# Power.net
KiCad netlist of a schematic drawn in Altium Designer
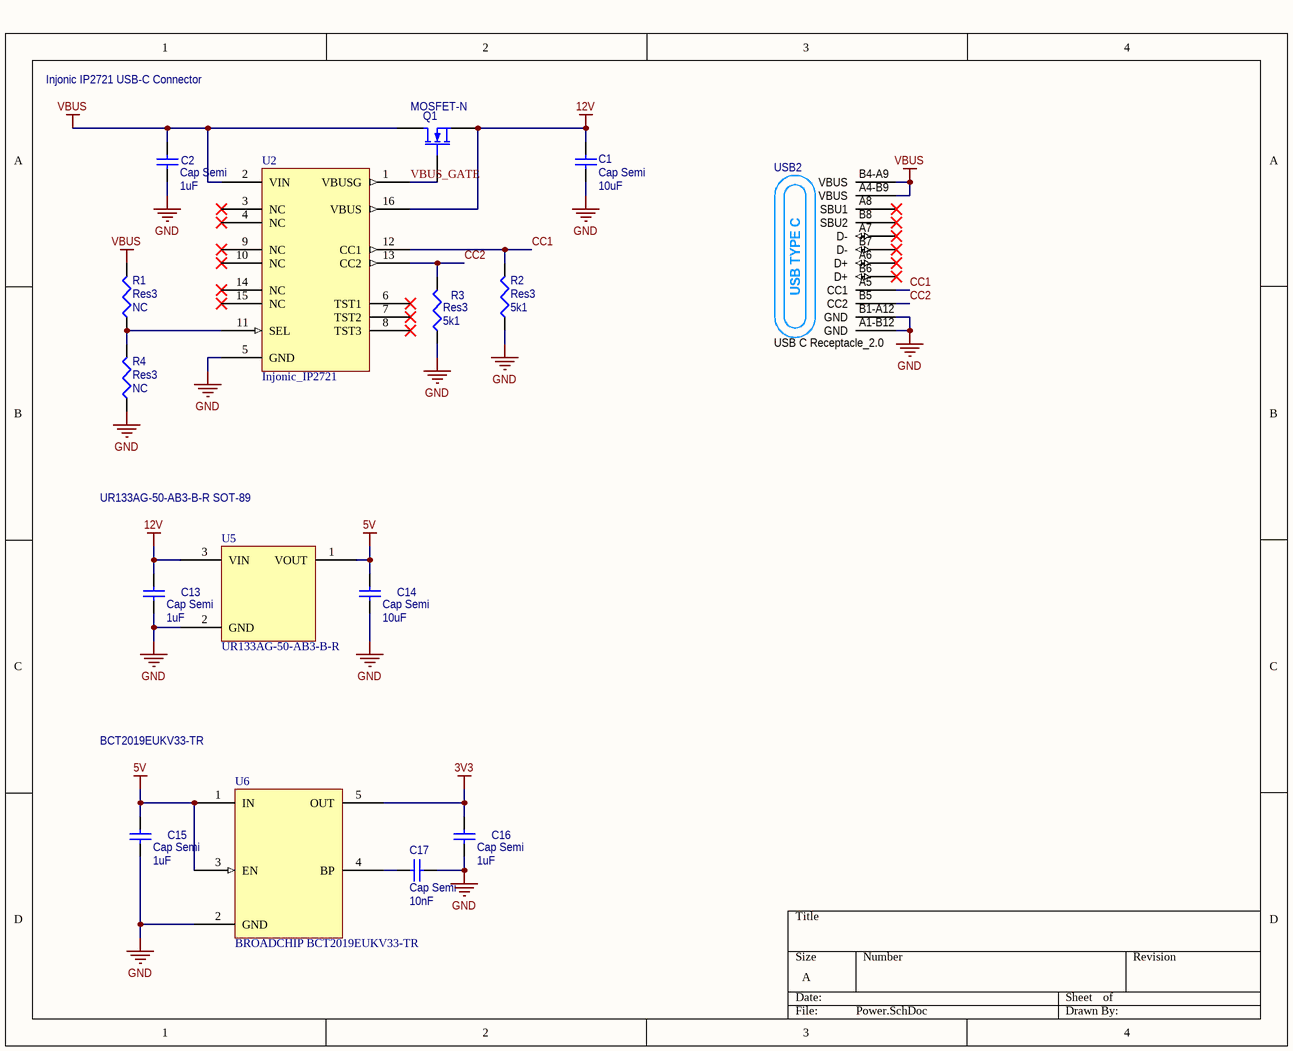
[diagram p0: Power.SchDoc]

(export (version "E")
  (design (tool "Eeschema 10.0.6"))
  (components
    (comp (ref "C1")
      (value "Cap Semi")
      (footprint "1608[0603]")
      (description "Capacitor (Semiconductor SIM Model)")
      (fields (field (name "ALTIUM_VALUE") "10uF") (field (name "PUBLISHER") "Altium Limited"))
      (libsource (lib "Miscellaneous Devices") (part "Cap Semi"))
    )
    (comp (ref "C2")
      (value "Cap Semi")
      (footprint "0402")
      (description "Capacitor (Semiconductor SIM Model)")
      (fields (field (name "ALTIUM_VALUE") "1uF") (field (name "PUBLISHER") "Altium Limited"))
      (libsource (lib "Miscellaneous Devices") (part "Cap Semi"))
    )
    (comp (ref "C13")
      (value "Cap Semi")
      (footprint "0402")
      (description "Capacitor (Semiconductor SIM Model)")
      (fields (field (name "ALTIUM_VALUE") "1uF") (field (name "PUBLISHER") "Altium Limited"))
      (libsource (lib "Miscellaneous Devices") (part "Cap Semi"))
    )
    (comp (ref "C14")
      (value "Cap Semi")
      (footprint "1608[0603]")
      (description "Capacitor (Semiconductor SIM Model)")
      (fields (field (name "ALTIUM_VALUE") "10uF") (field (name "PUBLISHER") "Altium Limited"))
      (libsource (lib "Miscellaneous Devices") (part "Cap Semi"))
    )
    (comp (ref "C15")
      (value "Cap Semi")
      (footprint "0402")
      (description "Capacitor (Semiconductor SIM Model)")
      (fields (field (name "ALTIUM_VALUE") "1uF") (field (name "PUBLISHER") "Altium Limited"))
      (libsource (lib "Miscellaneous Devices") (part "Cap Semi"))
    )
    (comp (ref "C16")
      (value "Cap Semi")
      (footprint "0402")
      (description "Capacitor (Semiconductor SIM Model)")
      (fields (field (name "ALTIUM_VALUE") "1uF") (field (name "PUBLISHER") "Altium Limited"))
      (libsource (lib "Miscellaneous Devices") (part "Cap Semi"))
    )
    (comp (ref "C17")
      (value "Cap Semi")
      (footprint "0402")
      (description "Capacitor (Semiconductor SIM Model)")
      (fields (field (name "ALTIUM_VALUE") "10nF") (field (name "PUBLISHER") "Altium Limited"))
      (libsource (lib "Miscellaneous Devices") (part "Cap Semi"))
    )
    (comp (ref "Q1")
      (value "MOSFET-N")
      (footprint "BSS214NWH6327")
      (description "N-Channel MOSFET")
      (fields (field (name "PUBLISHER") "Altium Limited"))
      (libsource (lib "Miscellaneous Devices") (part "MOSFET-N"))
    )
    (comp (ref "R1")
      (value "Res3")
      (footprint "J1-0603")
      (description "Resistor")
      (fields (field (name "ALTIUM_VALUE") "NC") (field (name "PUBLISHER") "Altium Limited"))
      (libsource (lib "Miscellaneous Devices") (part "Res3"))
    )
    (comp (ref "R2")
      (value "Res3")
      (footprint "J1-0603")
      (description "Resistor")
      (fields (field (name "ALTIUM_VALUE") "5k1") (field (name "PUBLISHER") "Altium Limited"))
      (libsource (lib "Miscellaneous Devices") (part "Res3"))
    )
    (comp (ref "R3")
      (value "Res3")
      (footprint "J1-0603")
      (description "Resistor")
      (fields (field (name "ALTIUM_VALUE") "5k1") (field (name "PUBLISHER") "Altium Limited"))
      (libsource (lib "Miscellaneous Devices") (part "Res3"))
    )
    (comp (ref "R4")
      (value "Res3")
      (footprint "J1-0603")
      (description "Resistor")
      (fields (field (name "ALTIUM_VALUE") "NC") (field (name "PUBLISHER") "Altium Limited"))
      (libsource (lib "Miscellaneous Devices") (part "Res3"))
    )
    (comp (ref "U2")
      (value "Injonic_IP2721")
      (footprint "TSOP65P640X120-16N")
      (description "USB-C Controller")
      (libsource (lib "Nixie_Clock") (part "Injonic_P2721"))
    )
    (comp (ref "U5")
      (value "UR133AG-50-AB3-B-R")
      (footprint "SOT89-150P415X160-3N")
      (description "12V-5V Voltage Regulator")
      (libsource (lib "Nixie_Clock") (part "UR133AG-50-AB3-B-R SOT-89"))
    )
    (comp (ref "U6")
      (value "BROADCHIP BCT2019EUKV33-TR")
      (footprint "SOT95P290X115-5N")
      (description "5V-3.3V Voltage Regulator")
      (libsource (lib "Nixie_Clock") (part "BCT2019EUKV33-TR"))
    )
    (comp (ref "USB2")
      (value "USB C Receptacle_2.0")
      (footprint "TYPE-C16PIN-CONNECTOR")
      (libsource (lib "kwa") (part "USB C Receptacle_2.0"))
    )
  )
  (nets
    (net (code "2") (name "/CC1") (class "Default")
      (node (ref "R2") (pin "2") (pinfunction "2_2") (pintype "passive"))
      (node (ref "U2") (pin "12") (pinfunction "CC1_12") (pintype "output"))
      (node (ref "USB2") (pin "A5") (pinfunction "CC1_A5") (pintype "passive"))
    )
    (net (code "3") (name "/CC2") (class "Default")
      (node (ref "R3") (pin "2") (pinfunction "2_2") (pintype "passive"))
      (node (ref "U2") (pin "13") (pinfunction "CC2_13") (pintype "output"))
      (node (ref "USB2") (pin "B5") (pinfunction "CC2_B5") (pintype "passive"))
    )
    (net (code "4") (name "/VBUS_GATE") (class "Default")
      (node (ref "Q1") (pin "2") (pinfunction "G_2") (pintype "passive"))
      (node (ref "U2") (pin "1") (pinfunction "VBUSG_1") (pintype "output"))
    )
    (net (code "5") (name "3V3") (class "Default")
      (node (ref "C16") (pin "2") (pinfunction "2_2") (pintype "passive"))
      (node (ref "U6") (pin "5") (pinfunction "OUT_5") (pintype "power_in"))
    )
    (net (code "6") (name "5V") (class "Default")
      (node (ref "C14") (pin "2") (pinfunction "2_2") (pintype "passive"))
      (node (ref "C15") (pin "2") (pinfunction "2_2") (pintype "passive"))
      (node (ref "U5") (pin "1") (pinfunction "VOUT_1") (pintype "power_in"))
      (node (ref "U6") (pin "1") (pinfunction "IN_1") (pintype "power_in"))
      (node (ref "U6") (pin "3") (pinfunction "EN_3") (pintype "input"))
    )
    (net (code "7") (name "12V") (class "Default")
      (node (ref "C1") (pin "2") (pinfunction "2_2") (pintype "passive"))
      (node (ref "C13") (pin "2") (pinfunction "2_2") (pintype "passive"))
      (node (ref "Q1") (pin "3") (pinfunction "S_3") (pintype "passive"))
      (node (ref "U2") (pin "16") (pinfunction "VBUS_16") (pintype "output"))
      (node (ref "U5") (pin "3") (pinfunction "VIN_3") (pintype "power_in"))
    )
    (net (code "8") (name "GND") (class "Default")
      (node (ref "C1") (pin "1") (pinfunction "1_1") (pintype "passive"))
      (node (ref "C13") (pin "1") (pinfunction "1_1") (pintype "passive"))
      (node (ref "C14") (pin "1") (pinfunction "1_1") (pintype "passive"))
      (node (ref "C15") (pin "1") (pinfunction "1_1") (pintype "passive"))
      (node (ref "C16") (pin "1") (pinfunction "1_1") (pintype "passive"))
      (node (ref "C17") (pin "1") (pinfunction "1_1") (pintype "passive"))
      (node (ref "C2") (pin "1") (pinfunction "1_1") (pintype "passive"))
      (node (ref "R2") (pin "1") (pinfunction "1_1") (pintype "passive"))
      (node (ref "R3") (pin "1") (pinfunction "1_1") (pintype "passive"))
      (node (ref "R4") (pin "1") (pinfunction "1_1") (pintype "passive"))
      (node (ref "U2") (pin "5") (pinfunction "GND_5") (pintype "power_in"))
      (node (ref "U5") (pin "2") (pinfunction "GND_2") (pintype "power_in"))
      (node (ref "U6") (pin "2") (pinfunction "GND_2") (pintype "power_in"))
      (node (ref "USB2") (pin "A1-B12") (pinfunction "GND_A1-B12") (pintype "power_in"))
      (node (ref "USB2") (pin "B1-A12") (pinfunction "GND_B1-A12") (pintype "power_in"))
    )
    (net (code "9") (name "Net-(U2-SEL)") (class "Default")
      (node (ref "R1") (pin "1") (pinfunction "1_1") (pintype "passive"))
      (node (ref "R4") (pin "2") (pinfunction "2_2") (pintype "passive"))
      (node (ref "U2") (pin "11") (pinfunction "SEL_11") (pintype "input"))
    )
    (net (code "10") (name "Net-(U6-BP)") (class "Default")
      (node (ref "C17") (pin "2") (pinfunction "2_2") (pintype "passive"))
      (node (ref "U6") (pin "4") (pinfunction "BP_4") (pintype "passive"))
    )
    (net (code "11") (name "VBUS") (class "Default")
      (node (ref "C2") (pin "2") (pinfunction "2_2") (pintype "passive"))
      (node (ref "Q1") (pin "1") (pinfunction "D_1") (pintype "passive"))
      (node (ref "R1") (pin "2") (pinfunction "2_2") (pintype "passive"))
      (node (ref "U2") (pin "2") (pinfunction "VIN_2") (pintype "power_in"))
      (node (ref "USB2") (pin "A4-B9") (pinfunction "VBUS_A4-B9") (pintype "power_in"))
      (node (ref "USB2") (pin "B4-A9") (pinfunction "VBUS_B4-A9") (pintype "power_in"))
    )
    (net (code "12") (name "unconnected-(U2-NC-Pad3)") (class "Default")
      (node (ref "U2") (pin "3") (pinfunction "NC_3") (pintype "passive+no_connect"))
    )
    (net (code "13") (name "unconnected-(U2-NC-Pad4)") (class "Default")
      (node (ref "U2") (pin "4") (pinfunction "NC_4") (pintype "passive+no_connect"))
    )
    (net (code "14") (name "unconnected-(U2-NC-Pad9)") (class "Default")
      (node (ref "U2") (pin "9") (pinfunction "NC_9") (pintype "passive+no_connect"))
    )
    (net (code "15") (name "unconnected-(U2-NC-Pad10)") (class "Default")
      (node (ref "U2") (pin "10") (pinfunction "NC_10") (pintype "passive+no_connect"))
    )
    (net (code "16") (name "unconnected-(U2-NC-Pad14)") (class "Default")
      (node (ref "U2") (pin "14") (pinfunction "NC_14") (pintype "passive+no_connect"))
    )
    (net (code "17") (name "unconnected-(U2-NC-Pad15)") (class "Default")
      (node (ref "U2") (pin "15") (pinfunction "NC_15") (pintype "passive+no_connect"))
    )
    (net (code "18") (name "unconnected-(U2-TST1-Pad6)") (class "Default")
      (node (ref "U2") (pin "6") (pinfunction "TST1_6") (pintype "passive+no_connect"))
    )
    (net (code "19") (name "unconnected-(U2-TST2-Pad7)") (class "Default")
      (node (ref "U2") (pin "7") (pinfunction "TST2_7") (pintype "passive+no_connect"))
    )
    (net (code "20") (name "unconnected-(U2-TST3-Pad8)") (class "Default")
      (node (ref "U2") (pin "8") (pinfunction "TST3_8") (pintype "passive+no_connect"))
    )
    (net (code "21") (name "unconnected-(USB2-D+-PadA6)") (class "Default")
      (node (ref "USB2") (pin "A6") (pinfunction "D+_A6") (pintype "bidirectional+no_connect"))
    )
    (net (code "22") (name "unconnected-(USB2-D+-PadB6)") (class "Default")
      (node (ref "USB2") (pin "B6") (pinfunction "D+_B6") (pintype "bidirectional+no_connect"))
    )
    (net (code "23") (name "unconnected-(USB2-D--PadA7)") (class "Default")
      (node (ref "USB2") (pin "A7") (pinfunction "D-_A7") (pintype "bidirectional+no_connect"))
    )
    (net (code "24") (name "unconnected-(USB2-D--PadB7)") (class "Default")
      (node (ref "USB2") (pin "B7") (pinfunction "D-_B7") (pintype "bidirectional+no_connect"))
    )
    (net (code "25") (name "unconnected-(USB2-SBU1-PadA8)") (class "Default")
      (node (ref "USB2") (pin "A8") (pinfunction "SBU1_A8") (pintype "passive+no_connect"))
    )
    (net (code "26") (name "unconnected-(USB2-SBU2-PadB8)") (class "Default")
      (node (ref "USB2") (pin "B8") (pinfunction "SBU2_B8") (pintype "passive+no_connect"))
    )
  )
)
